# curtains_stepper.net
KiCad netlist of a schematic drawn in EasyEDA
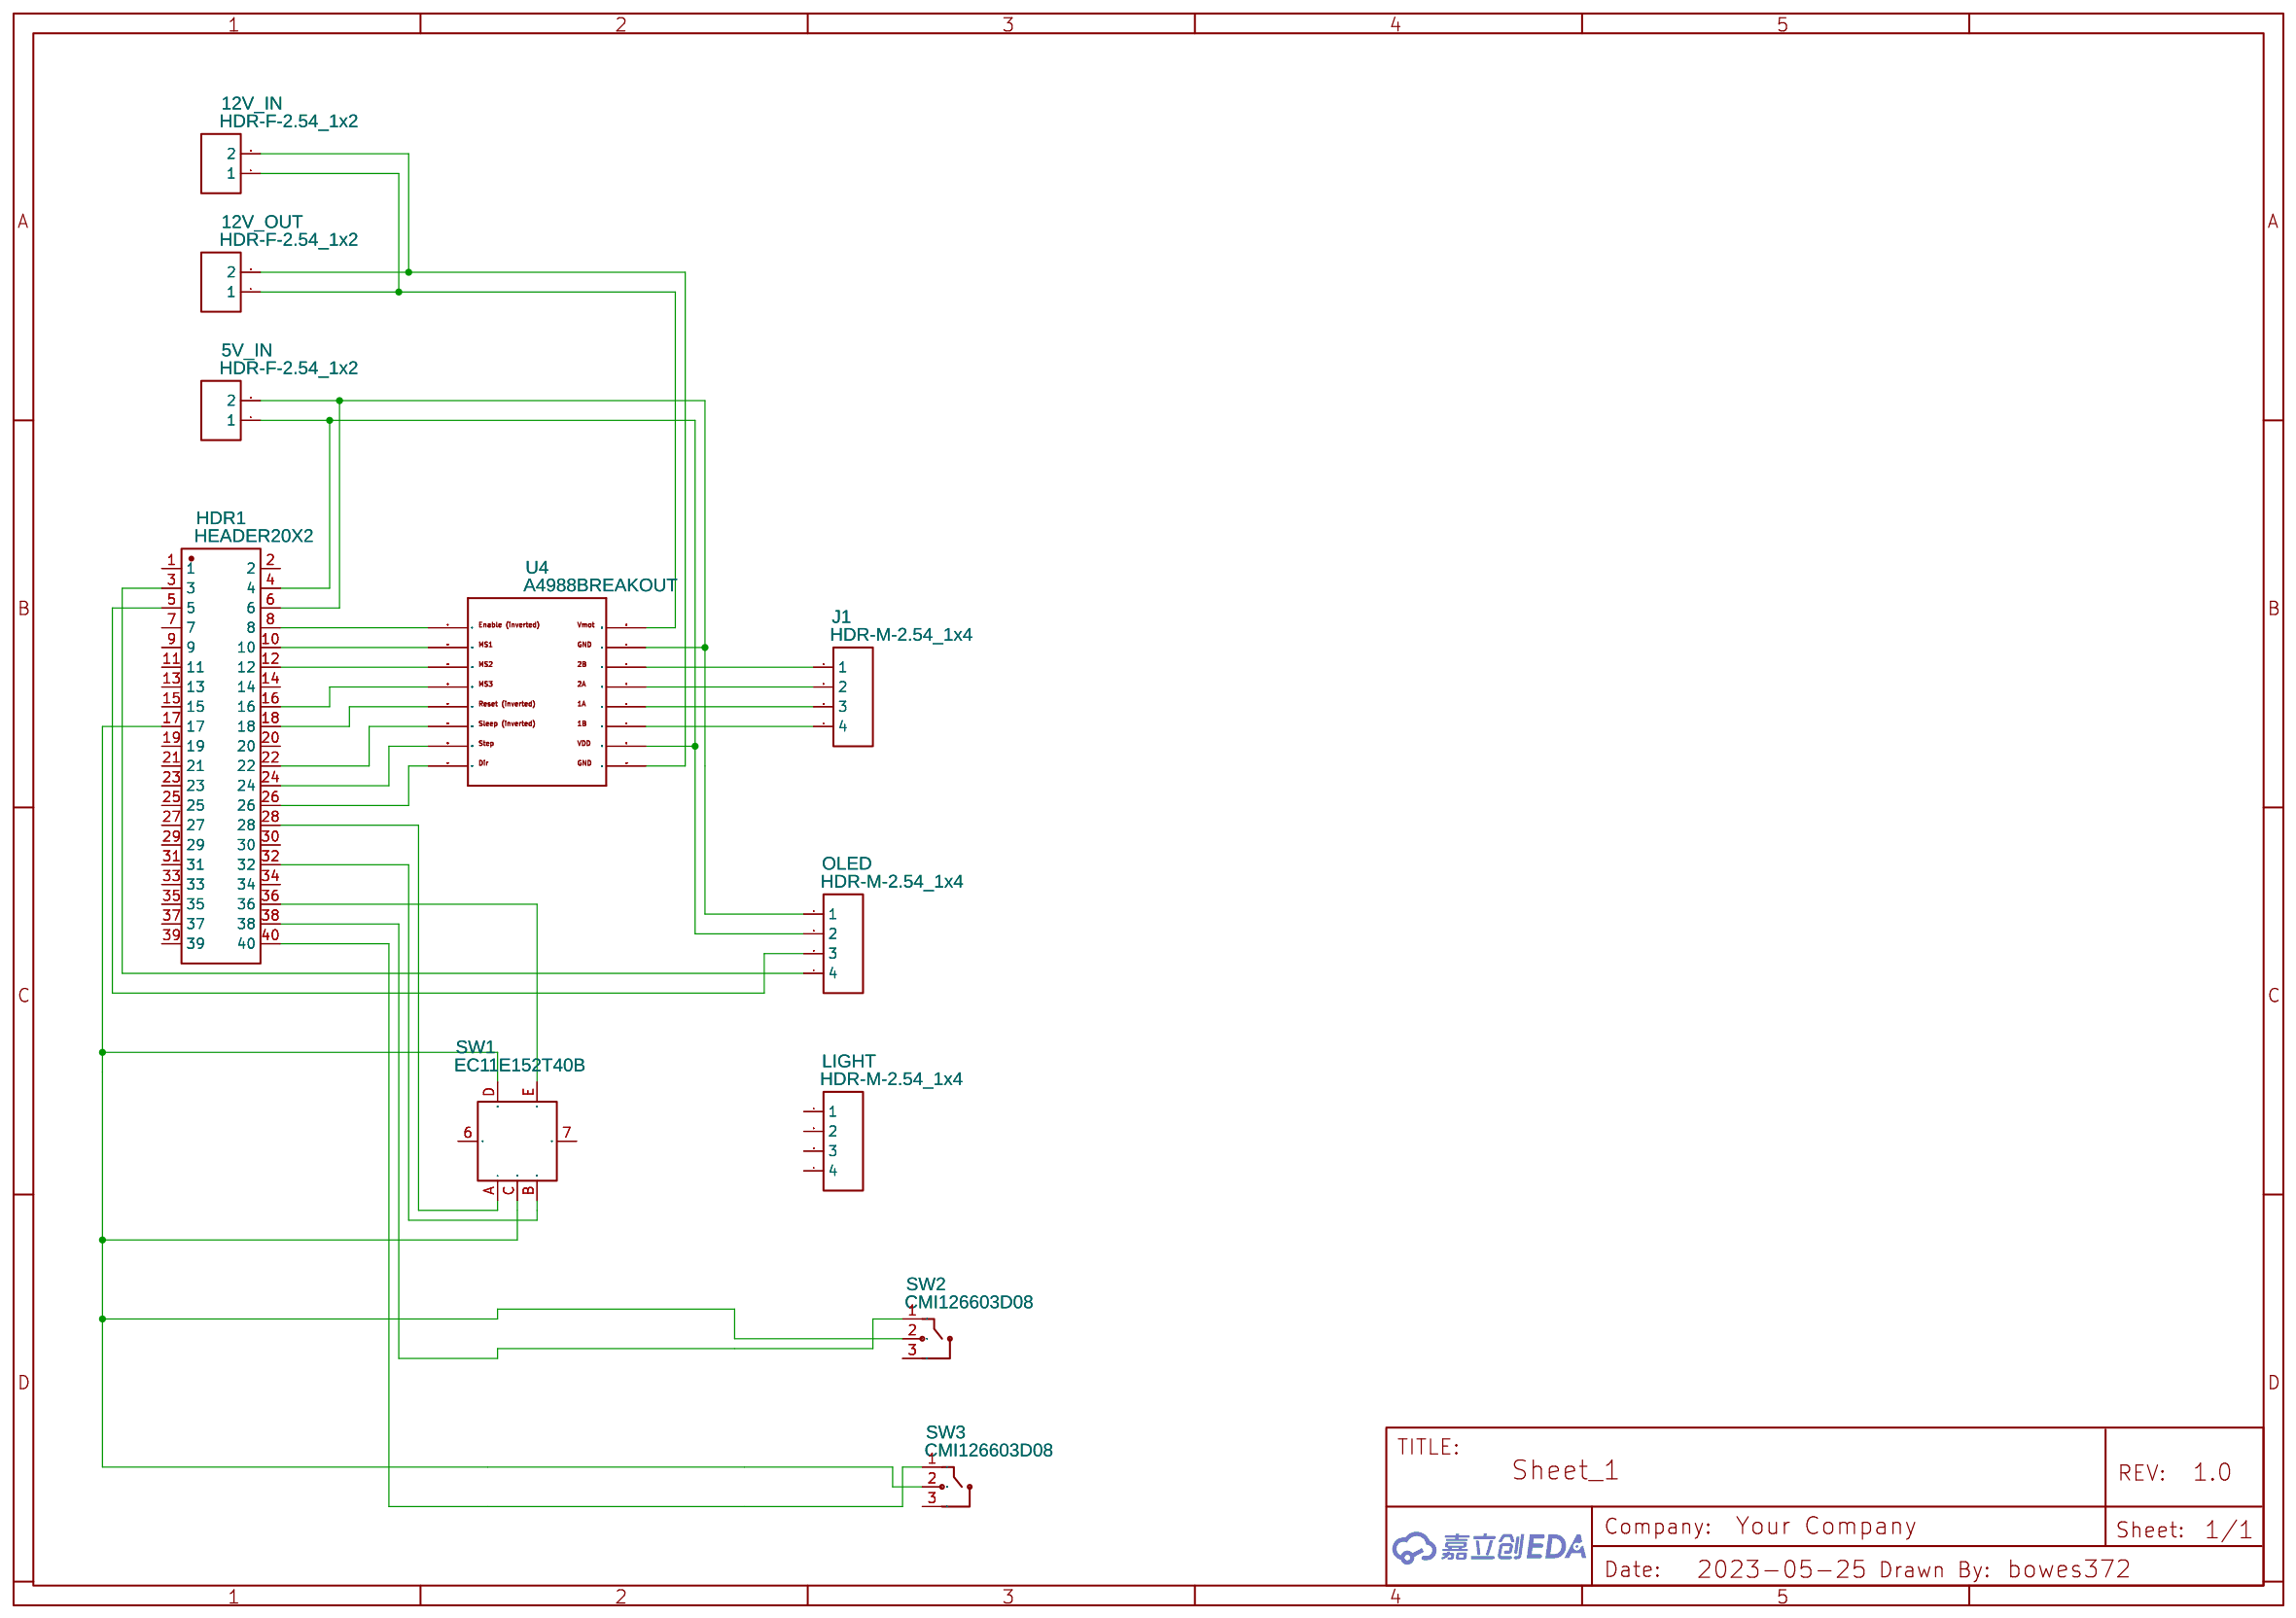
[diagram p0: schematic sheet]

(export (version "E")
  (design (tool "Eeschema 10.0.6"))
  (components
    (comp (ref "5V_IN")
      (value "HDR-F-2.54_1x2")
      (fields (field (name "BOM_Supplier Part") "C49661"))
      (libsource (lib "") (part "HDR-F-2.54_1x2_1"))
    )
    (comp (ref "12V_IN")
      (value "HDR-F-2.54_1x2")
      (fields (field (name "BOM_Supplier Part") "C49661"))
      (libsource (lib "") (part "HDR-F-2.54_1x2"))
    )
    (comp (ref "12V_OUT")
      (value "HDR-F-2.54_1x2")
      (fields (field (name "BOM_Supplier Part") "C49661"))
      (libsource (lib "") (part "HDR-F-2.54_1x2_2"))
    )
    (comp (ref "HDR1")
      (value "HEADER20X2")
      (fields
        (field (name "BOM_Manufacturer Part") "Header20X2")
        (field (name "BOM_Supplier Part") "C9900003702")
      )
      (libsource (lib "") (part "HEADER20X2"))
    )
    (comp (ref "J1")
      (value "HDR-M-2.54_1x4")
      (fields (field (name "BOM_Supplier Part") "C124378"))
      (libsource (lib "") (part "HDR-M-2.54_1x4_1"))
    )
    (comp (ref "LIGHT")
      (value "HDR-M-2.54_1x4")
      (fields (field (name "BOM_Supplier Part") "C124378"))
      (libsource (lib "") (part "HDR-M-2.54_1x4_2"))
    )
    (comp (ref "OLED")
      (value "HDR-M-2.54_1x4")
      (fields (field (name "BOM_Supplier Part") "C124378"))
      (libsource (lib "") (part "HDR-M-2.54_1x4"))
    )
    (comp (ref "SW1")
      (value "EC11E152T40B")
      (fields (field (name "BOM_Supplier Part") "C1322541"))
      (libsource (lib "") (part "EC11E152T40B"))
    )
    (comp (ref "SW2")
      (value "CMI126603D08")
      (fields (field (name "BOM_Supplier Part") "C400256"))
      (libsource (lib "") (part "CMI126603D08"))
    )
    (comp (ref "SW3")
      (value "CMI126603D08")
      (fields (field (name "BOM_Supplier Part") "C400256"))
      (libsource (lib "") (part "CMI126603D08"))
    )
    (comp (ref "U4") (value "A4988BREAKOUT") (libsource (lib "") (part "A4988BREAKOUT")))
  )
  (nets
    (net (code "1") (name "Net-(5V_IN-Pad1)") (class "Default")
      (node (ref "5V_IN") (pin "1") (pinfunction "1_1") (pintype "input"))
      (node (ref "HDR1") (pin "4") (pinfunction "4_4") (pintype "unspecified"))
      (node (ref "OLED") (pin "2") (pinfunction "2_2") (pintype "unspecified"))
      (node (ref "U4") (pin "VDD") (pinfunction "VDD_VDD") (pintype "bidirectional"))
    )
    (net (code "2") (name "Net-(5V_IN-Pad2)") (class "Default")
      (node (ref "5V_IN") (pin "2") (pinfunction "2_2") (pintype "input"))
      (node (ref "HDR1") (pin "6") (pinfunction "6_6") (pintype "unspecified"))
      (node (ref "OLED") (pin "1") (pinfunction "1_1") (pintype "unspecified"))
      (node (ref "U4") (pin "GND") (pinfunction "GND_GND") (pintype "bidirectional"))
    )
    (net (code "3") (name "Net-(12V_IN-Pad1)") (class "Default")
      (node (ref "12V_IN") (pin "1") (pinfunction "1_1") (pintype "input"))
      (node (ref "12V_OUT") (pin "1") (pinfunction "1_1") (pintype "input"))
      (node (ref "U4") (pin "VMOT") (pinfunction "VMOT_VMOT") (pintype "bidirectional"))
    )
    (net (code "4") (name "Net-(12V_IN-Pad2)") (class "Default")
      (node (ref "12V_IN") (pin "2") (pinfunction "2_2") (pintype "input"))
      (node (ref "12V_OUT") (pin "2") (pinfunction "2_2") (pintype "input"))
      (node (ref "U4") (pin "GND@0") (pinfunction "GND_GND@0") (pintype "bidirectional"))
    )
    (net (code "5") (name "Net-(HDR1-Pad3)") (class "Default")
      (node (ref "HDR1") (pin "3") (pinfunction "3_3") (pintype "unspecified"))
      (node (ref "OLED") (pin "4") (pinfunction "4_4") (pintype "unspecified"))
    )
    (net (code "6") (name "Net-(HDR1-Pad5)") (class "Default")
      (node (ref "HDR1") (pin "5") (pinfunction "5_5") (pintype "unspecified"))
      (node (ref "OLED") (pin "3") (pinfunction "3_3") (pintype "unspecified"))
    )
    (net (code "7") (name "Net-(HDR1-Pad8)") (class "Default")
      (node (ref "HDR1") (pin "8") (pinfunction "8_8") (pintype "unspecified"))
      (node (ref "U4") (pin "EN") (pinfunction "EN_EN") (pintype "bidirectional"))
    )
    (net (code "8") (name "Net-(HDR1-Pad10)") (class "Default")
      (node (ref "HDR1") (pin "10") (pinfunction "10_10") (pintype "unspecified"))
      (node (ref "U4") (pin "MS1") (pinfunction "MS1_MS1") (pintype "bidirectional"))
    )
    (net (code "9") (name "Net-(HDR1-Pad12)") (class "Default")
      (node (ref "HDR1") (pin "12") (pinfunction "12_12") (pintype "unspecified"))
      (node (ref "U4") (pin "MS2") (pinfunction "MS2_MS2") (pintype "bidirectional"))
    )
    (net (code "10") (name "Net-(HDR1-Pad16)") (class "Default")
      (node (ref "HDR1") (pin "16") (pinfunction "16_16") (pintype "unspecified"))
      (node (ref "U4") (pin "MS3") (pinfunction "MS3_MS3") (pintype "bidirectional"))
    )
    (net (code "11") (name "Net-(HDR1-Pad17)") (class "Default")
      (node (ref "HDR1") (pin "17") (pinfunction "17_17") (pintype "unspecified"))
      (node (ref "SW1") (pin "C") (pinfunction "C_C") (pintype "unspecified"))
      (node (ref "SW1") (pin "D") (pinfunction "D_D") (pintype "unspecified"))
      (node (ref "SW2") (pin "2") (pinfunction "2_2") (pintype "unspecified"))
      (node (ref "SW3") (pin "2") (pinfunction "2_2") (pintype "unspecified"))
    )
    (net (code "12") (name "Net-(HDR1-Pad18)") (class "Default")
      (node (ref "HDR1") (pin "18") (pinfunction "18_18") (pintype "unspecified"))
      (node (ref "U4") (pin "RST") (pinfunction "RST_RST") (pintype "bidirectional"))
    )
    (net (code "13") (name "Net-(HDR1-Pad24)") (class "Default")
      (node (ref "HDR1") (pin "24") (pinfunction "24_24") (pintype "unspecified"))
      (node (ref "U4") (pin "STEP") (pinfunction "STEP_STEP") (pintype "bidirectional"))
    )
    (net (code "14") (name "Net-(HDR1-Pad26)") (class "Default")
      (node (ref "HDR1") (pin "26") (pinfunction "26_26") (pintype "unspecified"))
      (node (ref "U4") (pin "DIR") (pinfunction "DIR_DIR") (pintype "bidirectional"))
    )
    (net (code "15") (name "Net-(HDR1-Pad28)") (class "Default")
      (node (ref "HDR1") (pin "28") (pinfunction "28_28") (pintype "unspecified"))
      (node (ref "SW1") (pin "A") (pinfunction "A_A") (pintype "unspecified"))
    )
    (net (code "16") (name "Net-(HDR1-Pad32)") (class "Default")
      (node (ref "HDR1") (pin "32") (pinfunction "32_32") (pintype "unspecified"))
      (node (ref "SW1") (pin "B") (pinfunction "B_B") (pintype "unspecified"))
    )
    (net (code "17") (name "Net-(HDR1-Pad36)") (class "Default")
      (node (ref "HDR1") (pin "36") (pinfunction "36_36") (pintype "unspecified"))
      (node (ref "SW1") (pin "E") (pinfunction "E_E") (pintype "unspecified"))
    )
    (net (code "18") (name "Net-(HDR1-Pad38)") (class "Default")
      (node (ref "HDR1") (pin "38") (pinfunction "38_38") (pintype "unspecified"))
      (node (ref "SW2") (pin "1") (pinfunction "1_1") (pintype "unspecified"))
    )
    (net (code "19") (name "Net-(HDR1-Pad40)") (class "Default")
      (node (ref "HDR1") (pin "40") (pinfunction "40_40") (pintype "unspecified"))
      (node (ref "SW3") (pin "1") (pinfunction "1_1") (pintype "unspecified"))
    )
    (net (code "20") (name "Net-(J1-Pad1)") (class "Default")
      (node (ref "J1") (pin "1") (pinfunction "1_1") (pintype "unspecified"))
      (node (ref "U4") (pin "2B") (pinfunction "2B_2B") (pintype "bidirectional"))
    )
    (net (code "21") (name "Net-(J1-Pad2)") (class "Default")
      (node (ref "J1") (pin "2") (pinfunction "2_2") (pintype "unspecified"))
      (node (ref "U4") (pin "2A") (pinfunction "2A_2A") (pintype "bidirectional"))
    )
    (net (code "22") (name "Net-(J1-Pad3)") (class "Default")
      (node (ref "J1") (pin "3") (pinfunction "3_3") (pintype "unspecified"))
      (node (ref "U4") (pin "1A") (pinfunction "1A_1A") (pintype "bidirectional"))
    )
    (net (code "23") (name "Net-(J1-Pad4)") (class "Default")
      (node (ref "J1") (pin "4") (pinfunction "4_4") (pintype "unspecified"))
      (node (ref "U4") (pin "1B") (pinfunction "1B_1B") (pintype "bidirectional"))
    )
    (net (code "24") (name "Net-(U4-SLEEP)") (class "Default")
      (node (ref "HDR1") (pin "22") (pinfunction "22_22") (pintype "unspecified"))
      (node (ref "U4") (pin "SLP") (pinfunction "SLEEP_SLP") (pintype "bidirectional"))
    )
    (net (code "25") (name "unconnected-(HDR1-Pad1)") (class "Default")
      (node (ref "HDR1") (pin "1") (pinfunction "1_1") (pintype "unspecified"))
    )
    (net (code "26") (name "unconnected-(HDR1-Pad2)") (class "Default")
      (node (ref "HDR1") (pin "2") (pinfunction "2_2") (pintype "unspecified"))
    )
    (net (code "27") (name "unconnected-(HDR1-Pad7)") (class "Default")
      (node (ref "HDR1") (pin "7") (pinfunction "7_7") (pintype "unspecified"))
    )
    (net (code "28") (name "unconnected-(HDR1-Pad9)") (class "Default")
      (node (ref "HDR1") (pin "9") (pinfunction "9_9") (pintype "unspecified"))
    )
    (net (code "29") (name "unconnected-(HDR1-Pad11)") (class "Default")
      (node (ref "HDR1") (pin "11") (pinfunction "11_11") (pintype "unspecified"))
    )
    (net (code "30") (name "unconnected-(HDR1-Pad13)") (class "Default")
      (node (ref "HDR1") (pin "13") (pinfunction "13_13") (pintype "unspecified"))
    )
    (net (code "31") (name "unconnected-(HDR1-Pad14)") (class "Default")
      (node (ref "HDR1") (pin "14") (pinfunction "14_14") (pintype "unspecified"))
    )
    (net (code "32") (name "unconnected-(HDR1-Pad15)") (class "Default")
      (node (ref "HDR1") (pin "15") (pinfunction "15_15") (pintype "unspecified"))
    )
    (net (code "33") (name "unconnected-(HDR1-Pad19)") (class "Default")
      (node (ref "HDR1") (pin "19") (pinfunction "19_19") (pintype "unspecified"))
    )
    (net (code "34") (name "unconnected-(HDR1-Pad20)") (class "Default")
      (node (ref "HDR1") (pin "20") (pinfunction "20_20") (pintype "unspecified"))
    )
    (net (code "35") (name "unconnected-(HDR1-Pad21)") (class "Default")
      (node (ref "HDR1") (pin "21") (pinfunction "21_21") (pintype "unspecified"))
    )
    (net (code "36") (name "unconnected-(HDR1-Pad23)") (class "Default")
      (node (ref "HDR1") (pin "23") (pinfunction "23_23") (pintype "unspecified"))
    )
    (net (code "37") (name "unconnected-(HDR1-Pad25)") (class "Default")
      (node (ref "HDR1") (pin "25") (pinfunction "25_25") (pintype "unspecified"))
    )
    (net (code "38") (name "unconnected-(HDR1-Pad27)") (class "Default")
      (node (ref "HDR1") (pin "27") (pinfunction "27_27") (pintype "unspecified"))
    )
    (net (code "39") (name "unconnected-(HDR1-Pad29)") (class "Default")
      (node (ref "HDR1") (pin "29") (pinfunction "29_29") (pintype "unspecified"))
    )
    (net (code "40") (name "unconnected-(HDR1-Pad30)") (class "Default")
      (node (ref "HDR1") (pin "30") (pinfunction "30_30") (pintype "unspecified"))
    )
    (net (code "41") (name "unconnected-(HDR1-Pad31)") (class "Default")
      (node (ref "HDR1") (pin "31") (pinfunction "31_31") (pintype "unspecified"))
    )
    (net (code "42") (name "unconnected-(HDR1-Pad33)") (class "Default")
      (node (ref "HDR1") (pin "33") (pinfunction "33_33") (pintype "unspecified"))
    )
    (net (code "43") (name "unconnected-(HDR1-Pad34)") (class "Default")
      (node (ref "HDR1") (pin "34") (pinfunction "34_34") (pintype "unspecified"))
    )
    (net (code "44") (name "unconnected-(HDR1-Pad35)") (class "Default")
      (node (ref "HDR1") (pin "35") (pinfunction "35_35") (pintype "unspecified"))
    )
    (net (code "45") (name "unconnected-(HDR1-Pad37)") (class "Default")
      (node (ref "HDR1") (pin "37") (pinfunction "37_37") (pintype "unspecified"))
    )
    (net (code "46") (name "unconnected-(HDR1-Pad39)") (class "Default")
      (node (ref "HDR1") (pin "39") (pinfunction "39_39") (pintype "unspecified"))
    )
    (net (code "47") (name "unconnected-(LIGHT-Pad1)") (class "Default")
      (node (ref "LIGHT") (pin "1") (pinfunction "1_1") (pintype "unspecified"))
    )
    (net (code "48") (name "unconnected-(LIGHT-Pad2)") (class "Default")
      (node (ref "LIGHT") (pin "2") (pinfunction "2_2") (pintype "unspecified"))
    )
    (net (code "49") (name "unconnected-(LIGHT-Pad3)") (class "Default")
      (node (ref "LIGHT") (pin "3") (pinfunction "3_3") (pintype "unspecified"))
    )
    (net (code "50") (name "unconnected-(LIGHT-Pad4)") (class "Default")
      (node (ref "LIGHT") (pin "4") (pinfunction "4_4") (pintype "unspecified"))
    )
    (net (code "51") (name "unconnected-(SW1-EH-Pad6)") (class "Default")
      (node (ref "SW1") (pin "6") (pinfunction "EH_6") (pintype "unspecified"))
    )
    (net (code "52") (name "unconnected-(SW1-EH-Pad7)") (class "Default")
      (node (ref "SW1") (pin "7") (pinfunction "EH_7") (pintype "unspecified"))
    )
    (net (code "53") (name "unconnected-(SW2-Pad3)") (class "Default")
      (node (ref "SW2") (pin "3") (pinfunction "3_3") (pintype "unspecified"))
    )
    (net (code "54") (name "unconnected-(SW3-Pad3)") (class "Default")
      (node (ref "SW3") (pin "3") (pinfunction "3_3") (pintype "unspecified"))
    )
  )
)
